# ControlPCB.net
KiCad netlist of a schematic drawn in EAGLE
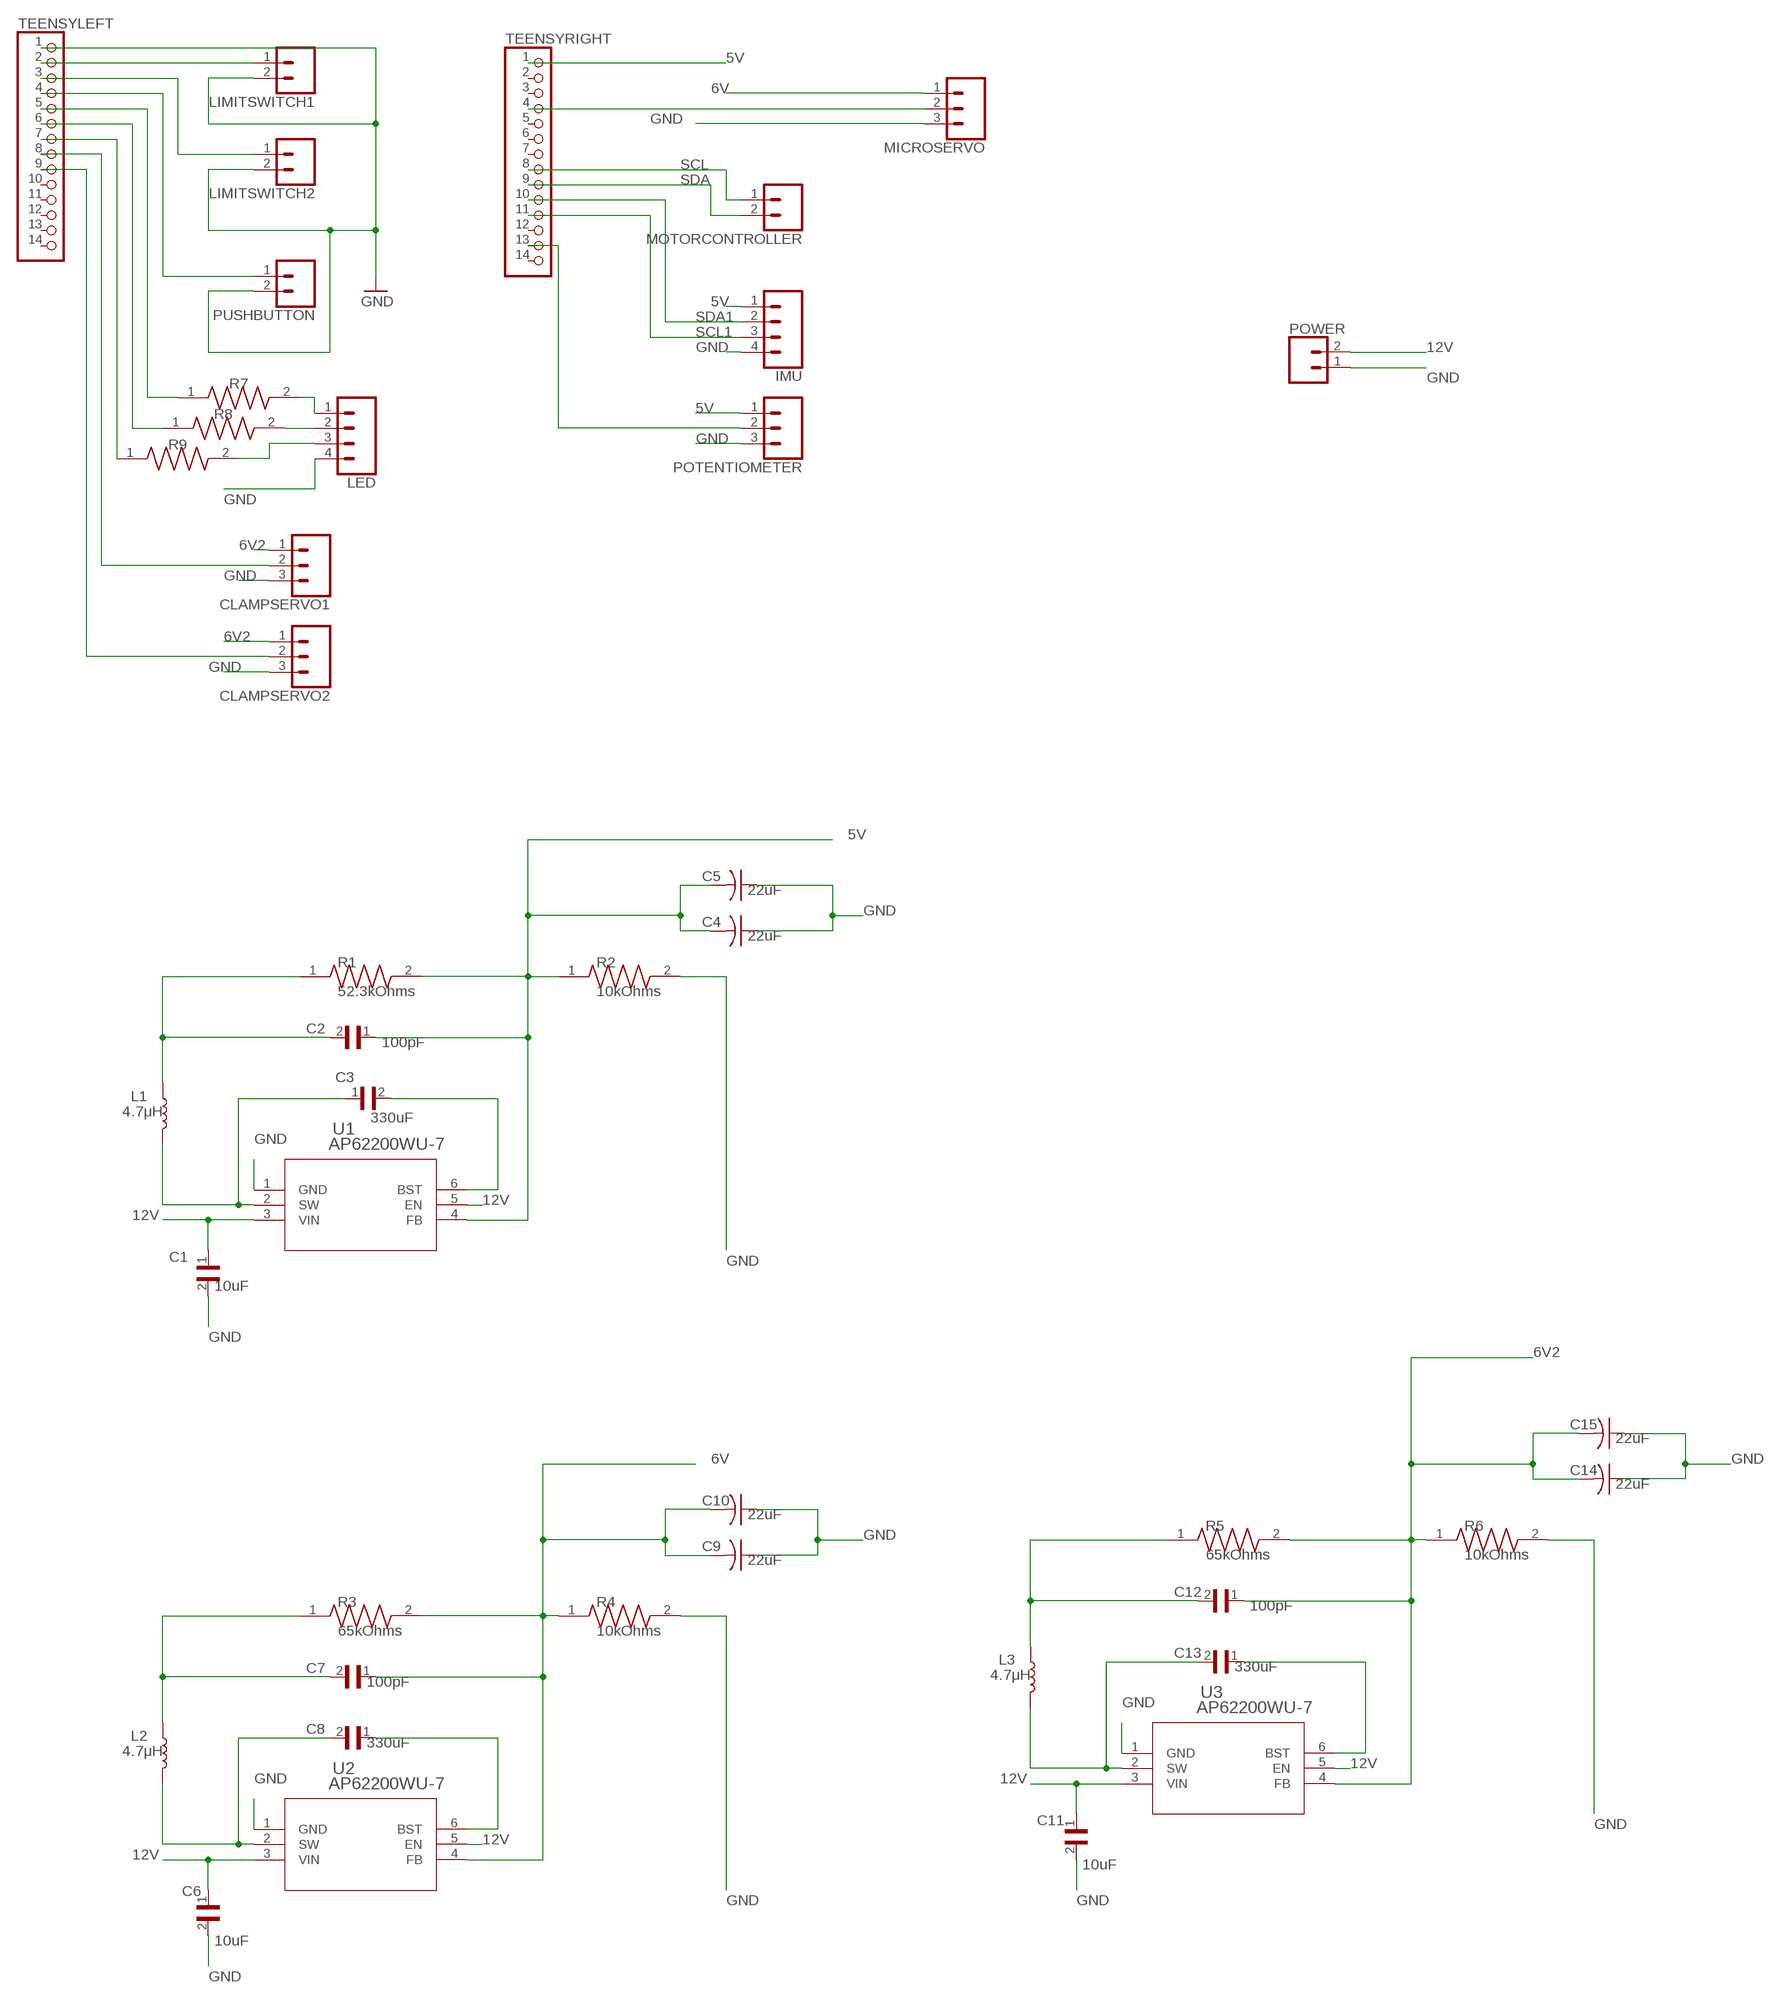
[diagram p0: schematic, sheet 1]

(export (version "E")
  (design (tool "Eeschema 10.0.6"))
  (components
    (comp (ref "C1")
      (value "10uF")
      (footprint "eagle-import:CAPC1608X90N")
      (libsource (lib "eagle-import") (part "JMK107BJ106MA-T"))
    )
    (comp (ref "C2")
      (value "100pF")
      (footprint "eagle-import:CAPC0603X33N")
      (libsource (lib "eagle-import") (part "GRM033R71E101KA01D"))
    )
    (comp (ref "C3")
      (value "330uF")
      (footprint "eagle-import:CAPC3225X280N")
      (libsource (lib "eagle-import") (part "GRM32EC80E337ME05K"))
    )
    (comp (ref "C4")
      (value "22uF")
      (footprint "eagle-import:C0402")
      (libsource (lib "eagle-import") (part "C-USC0402"))
    )
    (comp (ref "C5")
      (value "22uF")
      (footprint "eagle-import:C0402")
      (libsource (lib "eagle-import") (part "C-USC0402"))
    )
    (comp (ref "C6")
      (value "10uF")
      (footprint "eagle-import:CAPC1608X90N")
      (libsource (lib "eagle-import") (part "JMK107BJ106MA-T"))
    )
    (comp (ref "C7")
      (value "100pF")
      (footprint "eagle-import:CAPC0603X33N")
      (libsource (lib "eagle-import") (part "GRM033R71E101KA01D"))
    )
    (comp (ref "C8")
      (value "330uF")
      (footprint "eagle-import:CAPC3225X280N")
      (libsource (lib "eagle-import") (part "GRM32EC80E337ME05K"))
    )
    (comp (ref "C9")
      (value "22uF")
      (footprint "eagle-import:C0402")
      (libsource (lib "eagle-import") (part "C-USC0402"))
    )
    (comp (ref "C10")
      (value "22uF")
      (footprint "eagle-import:C0402")
      (libsource (lib "eagle-import") (part "C-USC0402"))
    )
    (comp (ref "C11")
      (value "10uF")
      (footprint "eagle-import:CAPC1608X90N")
      (libsource (lib "eagle-import") (part "JMK107BJ106MA-T"))
    )
    (comp (ref "C12")
      (value "100pF")
      (footprint "eagle-import:CAPC0603X33N")
      (libsource (lib "eagle-import") (part "GRM033R71E101KA01D"))
    )
    (comp (ref "C13")
      (value "330uF")
      (footprint "eagle-import:CAPC3225X280N")
      (libsource (lib "eagle-import") (part "GRM32EC80E337ME05K"))
    )
    (comp (ref "C14")
      (value "22uF")
      (footprint "eagle-import:C0402")
      (libsource (lib "eagle-import") (part "C-USC0402"))
    )
    (comp (ref "C15")
      (value "22uF")
      (footprint "eagle-import:C0402")
      (libsource (lib "eagle-import") (part "C-USC0402"))
    )
    (comp (ref "CLAMPSERVO1")
      (value "CONN_03SCREW")
      (footprint "eagle-import:SCREWTERMINAL-3.5MM-3")
      (libsource (lib "eagle-import") (part "CONN_03SCREW"))
    )
    (comp (ref "CLAMPSERVO2")
      (value "CONN_03SCREW")
      (footprint "eagle-import:SCREWTERMINAL-3.5MM-3")
      (libsource (lib "eagle-import") (part "CONN_03SCREW"))
    )
    (comp (ref "IMU")
      (value "CONN_04SCREW")
      (footprint "eagle-import:SCREWTERMINAL-3.5MM-4")
      (libsource (lib "eagle-import") (part "CONN_04SCREW"))
    )
    (comp (ref "L1")
      (value "4.7μH")
      (footprint "eagle-import:INDUCTOR_4X4MM")
      (libsource (lib "eagle-import") (part "4.7μH_SHIELDED_INDUCTORNPIS_LS"))
    )
    (comp (ref "L2")
      (value "4.7μH")
      (footprint "eagle-import:INDUCTOR_4X4MM")
      (libsource (lib "eagle-import") (part "4.7μH_SHIELDED_INDUCTORNPIS_LS"))
    )
    (comp (ref "L3")
      (value "4.7μH")
      (footprint "eagle-import:INDUCTOR_4X4MM")
      (libsource (lib "eagle-import") (part "4.7μH_SHIELDED_INDUCTORNPIS_LS"))
    )
    (comp (ref "LED")
      (value "CONN_04SCREW")
      (footprint "eagle-import:SCREWTERMINAL-3.5MM-4")
      (libsource (lib "eagle-import") (part "CONN_04SCREW"))
    )
    (comp (ref "LIMITSWITCH1")
      (value "CONN_023.5MM")
      (footprint "eagle-import:SCREWTERMINAL-3.5MM-2")
      (libsource (lib "eagle-import") (part "CONN_023.5MM"))
    )
    (comp (ref "LIMITSWITCH2")
      (value "CONN_023.5MM")
      (footprint "eagle-import:SCREWTERMINAL-3.5MM-2")
      (libsource (lib "eagle-import") (part "CONN_023.5MM"))
    )
    (comp (ref "MICROSERVO")
      (value "CONN_03SCREW")
      (footprint "eagle-import:SCREWTERMINAL-3.5MM-3")
      (libsource (lib "eagle-import") (part "CONN_03SCREW"))
    )
    (comp (ref "MOTORCONTROLLER")
      (value "CONN_023.5MM")
      (footprint "eagle-import:SCREWTERMINAL-3.5MM-2")
      (libsource (lib "eagle-import") (part "CONN_023.5MM"))
    )
    (comp (ref "POTENTIOMETER")
      (value "CONN_03SCREW")
      (footprint "eagle-import:SCREWTERMINAL-3.5MM-3")
      (libsource (lib "eagle-import") (part "CONN_03SCREW"))
    )
    (comp (ref "POWER")
      (value "CONN_023.5MM")
      (footprint "eagle-import:SCREWTERMINAL-3.5MM-2")
      (libsource (lib "eagle-import") (part "CONN_023.5MM"))
    )
    (comp (ref "PUSHBUTTON")
      (value "CONN_023.5MM")
      (footprint "eagle-import:SCREWTERMINAL-3.5MM-2")
      (libsource (lib "eagle-import") (part "CONN_023.5MM"))
    )
    (comp (ref "R1")
      (value "52.3kOhms")
      (footprint "eagle-import:RES_ERJ1GNF1000C")
      (fields (field (name "MANUFACTURER") "Panasonic"))
      (libsource (lib "eagle-import") (part "ERJ1GNF1000C"))
    )
    (comp (ref "R2")
      (value "10kOhms")
      (footprint "eagle-import:RES_ERJ1GNF1000C")
      (fields (field (name "MANUFACTURER") "Panasonic"))
      (libsource (lib "eagle-import") (part "ERJ1GNF1000C"))
    )
    (comp (ref "R3")
      (value "65kOhms")
      (footprint "eagle-import:RES_ERJ1GNF1000C")
      (fields (field (name "MANUFACTURER") "Panasonic"))
      (libsource (lib "eagle-import") (part "ERJ1GNF1000C"))
    )
    (comp (ref "R4")
      (value "10kOhms")
      (footprint "eagle-import:RES_ERJ1GNF1000C")
      (fields (field (name "MANUFACTURER") "Panasonic"))
      (libsource (lib "eagle-import") (part "ERJ1GNF1000C"))
    )
    (comp (ref "R5")
      (value "65kOhms")
      (footprint "eagle-import:RES_ERJ1GNF1000C")
      (fields (field (name "MANUFACTURER") "Panasonic"))
      (libsource (lib "eagle-import") (part "ERJ1GNF1000C"))
    )
    (comp (ref "R6")
      (value "10kOhms")
      (footprint "eagle-import:RES_ERJ1GNF1000C")
      (fields (field (name "MANUFACTURER") "Panasonic"))
      (libsource (lib "eagle-import") (part "ERJ1GNF1000C"))
    )
    (comp (ref "R7")
      (value "100Ohm")
      (footprint "eagle-import:RES_ERJ1GNF1000C")
      (fields (field (name "MANUFACTURER") "Panasonic"))
      (libsource (lib "eagle-import") (part "ERJ1GNF1000C"))
    )
    (comp (ref "R8")
      (value "100Ohm")
      (footprint "eagle-import:RES_ERJ1GNF1000C")
      (fields (field (name "MANUFACTURER") "Panasonic"))
      (libsource (lib "eagle-import") (part "ERJ1GNF1000C"))
    )
    (comp (ref "R9")
      (value "100Ohm")
      (footprint "eagle-import:RES_ERJ1GNF1000C")
      (fields (field (name "MANUFACTURER") "Panasonic"))
      (libsource (lib "eagle-import") (part "ERJ1GNF1000C"))
    )
    (comp (ref "TEENSYLEFT")
      (value "PINHD-1X14")
      (footprint "eagle-import:1X14")
      (libsource (lib "eagle-import") (part "PINHD-1X14"))
    )
    (comp (ref "TEENSYRIGHT")
      (value "PINHD-1X14")
      (footprint "eagle-import:1X14")
      (libsource (lib "eagle-import") (part "PINHD-1X14"))
    )
    (comp (ref "U1")
      (value "AP62200WU-7")
      (footprint "eagle-import:TSOT26-WU_DIO")
      (fields (field (name "COPYRIGHT") "Copyright (C) 2023 Ultra Librarian. All rights reserved."))
      (libsource (lib "eagle-import") (part "AP62200WU-7"))
    )
    (comp (ref "U2")
      (value "AP62200WU-7")
      (footprint "eagle-import:TSOT26-WU_DIO")
      (fields (field (name "COPYRIGHT") "Copyright (C) 2023 Ultra Librarian. All rights reserved."))
      (libsource (lib "eagle-import") (part "AP62200WU-7"))
    )
    (comp (ref "U3")
      (value "AP62200WU-7")
      (footprint "eagle-import:TSOT26-WU_DIO")
      (fields (field (name "COPYRIGHT") "Copyright (C) 2023 Ultra Librarian. All rights reserved."))
      (libsource (lib "eagle-import") (part "AP62200WU-7"))
    )
  )
  (nets
    (net (code "1") (name "/5V") (class "Default")
      (node (ref "C2") (pin "1") (pinfunction "1_1") (pintype "passive"))
      (node (ref "C4") (pin "2") (pinfunction "2_2") (pintype "passive"))
      (node (ref "C5") (pin "2") (pinfunction "2_2") (pintype "passive"))
      (node (ref "IMU") (pin "1") (pinfunction "1_1") (pintype "passive"))
      (node (ref "POTENTIOMETER") (pin "1") (pinfunction "1_1") (pintype "passive"))
      (node (ref "R1") (pin "2") (pinfunction "2_2") (pintype "passive"))
      (node (ref "R2") (pin "1") (pinfunction "1_1") (pintype "passive"))
      (node (ref "TEENSYRIGHT") (pin "1") (pinfunction "1_1") (pintype "passive"))
      (node (ref "U1") (pin "4") (pinfunction "FB_4") (pintype "passive"))
    )
    (net (code "2") (name "/6V") (class "Default")
      (node (ref "C10") (pin "2") (pinfunction "2_2") (pintype "passive"))
      (node (ref "C7") (pin "1") (pinfunction "1_1") (pintype "passive"))
      (node (ref "C9") (pin "2") (pinfunction "2_2") (pintype "passive"))
      (node (ref "MICROSERVO") (pin "1") (pinfunction "1_1") (pintype "passive"))
      (node (ref "R3") (pin "2") (pinfunction "2_2") (pintype "passive"))
      (node (ref "R4") (pin "1") (pinfunction "1_1") (pintype "passive"))
      (node (ref "U2") (pin "4") (pinfunction "FB_4") (pintype "passive"))
    )
    (net (code "3") (name "/6V2") (class "Default")
      (node (ref "C12") (pin "1") (pinfunction "1_1") (pintype "passive"))
      (node (ref "C14") (pin "2") (pinfunction "2_2") (pintype "passive"))
      (node (ref "C15") (pin "2") (pinfunction "2_2") (pintype "passive"))
      (node (ref "CLAMPSERVO1") (pin "1") (pinfunction "1_1") (pintype "passive"))
      (node (ref "CLAMPSERVO2") (pin "1") (pinfunction "1_1") (pintype "passive"))
      (node (ref "R5") (pin "2") (pinfunction "2_2") (pintype "passive"))
      (node (ref "R6") (pin "1") (pinfunction "1_1") (pintype "passive"))
      (node (ref "U3") (pin "4") (pinfunction "FB_4") (pintype "passive"))
    )
    (net (code "4") (name "/12V") (class "Default")
      (node (ref "C1") (pin "1") (pinfunction "1_1") (pintype "passive"))
      (node (ref "C11") (pin "1") (pinfunction "1_1") (pintype "passive"))
      (node (ref "C6") (pin "1") (pinfunction "1_1") (pintype "passive"))
      (node (ref "POWER") (pin "2") (pinfunction "2_2") (pintype "passive"))
      (node (ref "U1") (pin "3") (pinfunction "VIN_3") (pintype "power_in"))
      (node (ref "U1") (pin "5") (pinfunction "EN_5") (pintype "input"))
      (node (ref "U2") (pin "3") (pinfunction "VIN_3") (pintype "power_in"))
      (node (ref "U2") (pin "5") (pinfunction "EN_5") (pintype "input"))
      (node (ref "U3") (pin "3") (pinfunction "VIN_3") (pintype "power_in"))
      (node (ref "U3") (pin "5") (pinfunction "EN_5") (pintype "input"))
    )
    (net (code "5") (name "/SCL") (class "Default")
      (node (ref "MOTORCONTROLLER") (pin "1") (pinfunction "1_1") (pintype "passive"))
      (node (ref "TEENSYRIGHT") (pin "8") (pinfunction "8_8") (pintype "passive"))
    )
    (net (code "6") (name "/SCL1") (class "Default")
      (node (ref "IMU") (pin "3") (pinfunction "3_3") (pintype "passive"))
      (node (ref "TEENSYRIGHT") (pin "11") (pinfunction "11_11") (pintype "passive"))
    )
    (net (code "7") (name "/SDA") (class "Default")
      (node (ref "MOTORCONTROLLER") (pin "2") (pinfunction "2_2") (pintype "passive"))
      (node (ref "TEENSYRIGHT") (pin "9") (pinfunction "9_9") (pintype "passive"))
    )
    (net (code "8") (name "/SDA1") (class "Default")
      (node (ref "IMU") (pin "2") (pinfunction "2_2") (pintype "passive"))
      (node (ref "TEENSYRIGHT") (pin "10") (pinfunction "10_10") (pintype "passive"))
    )
    (net (code "9") (name "GND") (class "Default")
      (node (ref "C1") (pin "2") (pinfunction "2_2") (pintype "passive"))
      (node (ref "C10") (pin "1") (pinfunction "1_1") (pintype "passive"))
      (node (ref "C11") (pin "2") (pinfunction "2_2") (pintype "passive"))
      (node (ref "C14") (pin "1") (pinfunction "1_1") (pintype "passive"))
      (node (ref "C15") (pin "1") (pinfunction "1_1") (pintype "passive"))
      (node (ref "C4") (pin "1") (pinfunction "1_1") (pintype "passive"))
      (node (ref "C5") (pin "1") (pinfunction "1_1") (pintype "passive"))
      (node (ref "C6") (pin "2") (pinfunction "2_2") (pintype "passive"))
      (node (ref "C9") (pin "1") (pinfunction "1_1") (pintype "passive"))
      (node (ref "CLAMPSERVO1") (pin "3") (pinfunction "3_3") (pintype "passive"))
      (node (ref "CLAMPSERVO2") (pin "3") (pinfunction "3_3") (pintype "passive"))
      (node (ref "IMU") (pin "4") (pinfunction "4_4") (pintype "passive"))
      (node (ref "LED") (pin "4") (pinfunction "4_4") (pintype "passive"))
      (node (ref "LIMITSWITCH1") (pin "2") (pinfunction "2_2") (pintype "passive"))
      (node (ref "LIMITSWITCH2") (pin "2") (pinfunction "2_2") (pintype "passive"))
      (node (ref "MICROSERVO") (pin "3") (pinfunction "3_3") (pintype "passive"))
      (node (ref "POTENTIOMETER") (pin "3") (pinfunction "3_3") (pintype "passive"))
      (node (ref "POWER") (pin "1") (pinfunction "1_1") (pintype "passive"))
      (node (ref "PUSHBUTTON") (pin "2") (pinfunction "2_2") (pintype "passive"))
      (node (ref "R2") (pin "2") (pinfunction "2_2") (pintype "passive"))
      (node (ref "R4") (pin "2") (pinfunction "2_2") (pintype "passive"))
      (node (ref "R6") (pin "2") (pinfunction "2_2") (pintype "passive"))
      (node (ref "TEENSYLEFT") (pin "1") (pinfunction "1_1") (pintype "passive"))
      (node (ref "U1") (pin "1") (pinfunction "GND_1") (pintype "passive"))
      (node (ref "U2") (pin "1") (pinfunction "GND_1") (pintype "passive"))
      (node (ref "U3") (pin "1") (pinfunction "GND_1") (pintype "passive"))
    )
    (net (code "10") (name "Net-(CLAMPSERVO1-Pad2)") (class "Default")
      (node (ref "CLAMPSERVO1") (pin "2") (pinfunction "2_2") (pintype "passive"))
      (node (ref "TEENSYLEFT") (pin "8") (pinfunction "8_8") (pintype "passive"))
    )
    (net (code "11") (name "Net-(CLAMPSERVO2-Pad2)") (class "Default")
      (node (ref "CLAMPSERVO2") (pin "2") (pinfunction "2_2") (pintype "passive"))
      (node (ref "TEENSYLEFT") (pin "9") (pinfunction "9_9") (pintype "passive"))
    )
    (net (code "12") (name "Net-(L1-1)") (class "Default")
      (node (ref "C2") (pin "2") (pinfunction "2_2") (pintype "passive"))
      (node (ref "L1") (pin "P$1") (pinfunction "1_P$1") (pintype "passive"))
      (node (ref "R1") (pin "1") (pinfunction "1_1") (pintype "passive"))
    )
    (net (code "13") (name "Net-(L1-2)") (class "Default")
      (node (ref "C3") (pin "1") (pinfunction "1_1") (pintype "passive"))
      (node (ref "L1") (pin "P$2") (pinfunction "2_P$2") (pintype "passive"))
      (node (ref "U1") (pin "2") (pinfunction "SW_2") (pintype "passive"))
    )
    (net (code "14") (name "Net-(L2-1)") (class "Default")
      (node (ref "C7") (pin "2") (pinfunction "2_2") (pintype "passive"))
      (node (ref "L2") (pin "P$1") (pinfunction "1_P$1") (pintype "passive"))
      (node (ref "R3") (pin "1") (pinfunction "1_1") (pintype "passive"))
    )
    (net (code "15") (name "Net-(L2-2)") (class "Default")
      (node (ref "C8") (pin "2") (pinfunction "2_2") (pintype "passive"))
      (node (ref "L2") (pin "P$2") (pinfunction "2_P$2") (pintype "passive"))
      (node (ref "U2") (pin "2") (pinfunction "SW_2") (pintype "passive"))
    )
    (net (code "16") (name "Net-(L3-1)") (class "Default")
      (node (ref "C12") (pin "2") (pinfunction "2_2") (pintype "passive"))
      (node (ref "L3") (pin "P$1") (pinfunction "1_P$1") (pintype "passive"))
      (node (ref "R5") (pin "1") (pinfunction "1_1") (pintype "passive"))
    )
    (net (code "17") (name "Net-(L3-2)") (class "Default")
      (node (ref "C13") (pin "2") (pinfunction "2_2") (pintype "passive"))
      (node (ref "L3") (pin "P$2") (pinfunction "2_P$2") (pintype "passive"))
      (node (ref "U3") (pin "2") (pinfunction "SW_2") (pintype "passive"))
    )
    (net (code "18") (name "Net-(LED-Pad1)") (class "Default")
      (node (ref "LED") (pin "1") (pinfunction "1_1") (pintype "passive"))
      (node (ref "R7") (pin "2") (pinfunction "2_2") (pintype "passive"))
    )
    (net (code "19") (name "Net-(LED-Pad2)") (class "Default")
      (node (ref "LED") (pin "2") (pinfunction "2_2") (pintype "passive"))
      (node (ref "R8") (pin "2") (pinfunction "2_2") (pintype "passive"))
    )
    (net (code "20") (name "Net-(LED-Pad3)") (class "Default")
      (node (ref "LED") (pin "3") (pinfunction "3_3") (pintype "passive"))
      (node (ref "R9") (pin "2") (pinfunction "2_2") (pintype "passive"))
    )
    (net (code "21") (name "Net-(LIMITSWITCH1-Pad1)") (class "Default")
      (node (ref "LIMITSWITCH1") (pin "1") (pinfunction "1_1") (pintype "passive"))
      (node (ref "TEENSYLEFT") (pin "2") (pinfunction "2_2") (pintype "passive"))
    )
    (net (code "22") (name "Net-(LIMITSWITCH2-Pad1)") (class "Default")
      (node (ref "LIMITSWITCH2") (pin "1") (pinfunction "1_1") (pintype "passive"))
      (node (ref "TEENSYLEFT") (pin "3") (pinfunction "3_3") (pintype "passive"))
    )
    (net (code "23") (name "Net-(MICROSERVO-Pad2)") (class "Default")
      (node (ref "MICROSERVO") (pin "2") (pinfunction "2_2") (pintype "passive"))
      (node (ref "TEENSYRIGHT") (pin "4") (pinfunction "4_4") (pintype "passive"))
    )
    (net (code "24") (name "Net-(POTENTIOMETER-Pad2)") (class "Default")
      (node (ref "POTENTIOMETER") (pin "2") (pinfunction "2_2") (pintype "passive"))
      (node (ref "TEENSYRIGHT") (pin "13") (pinfunction "13_13") (pintype "passive"))
    )
    (net (code "25") (name "Net-(PUSHBUTTON-Pad1)") (class "Default")
      (node (ref "PUSHBUTTON") (pin "1") (pinfunction "1_1") (pintype "passive"))
      (node (ref "TEENSYLEFT") (pin "4") (pinfunction "4_4") (pintype "passive"))
    )
    (net (code "26") (name "Net-(R7-Pad1)") (class "Default")
      (node (ref "R7") (pin "1") (pinfunction "1_1") (pintype "passive"))
      (node (ref "TEENSYLEFT") (pin "5") (pinfunction "5_5") (pintype "passive"))
    )
    (net (code "27") (name "Net-(R8-Pad1)") (class "Default")
      (node (ref "R8") (pin "1") (pinfunction "1_1") (pintype "passive"))
      (node (ref "TEENSYLEFT") (pin "6") (pinfunction "6_6") (pintype "passive"))
    )
    (net (code "28") (name "Net-(R9-Pad1)") (class "Default")
      (node (ref "R9") (pin "1") (pinfunction "1_1") (pintype "passive"))
      (node (ref "TEENSYLEFT") (pin "7") (pinfunction "7_7") (pintype "passive"))
    )
    (net (code "29") (name "Net-(U1-BST)") (class "Default")
      (node (ref "C3") (pin "2") (pinfunction "2_2") (pintype "passive"))
      (node (ref "U1") (pin "6") (pinfunction "BST_6") (pintype "input"))
    )
    (net (code "30") (name "Net-(U2-BST)") (class "Default")
      (node (ref "C8") (pin "1") (pinfunction "1_1") (pintype "passive"))
      (node (ref "U2") (pin "6") (pinfunction "BST_6") (pintype "input"))
    )
    (net (code "31") (name "Net-(U3-BST)") (class "Default")
      (node (ref "C13") (pin "1") (pinfunction "1_1") (pintype "passive"))
      (node (ref "U3") (pin "6") (pinfunction "BST_6") (pintype "input"))
    )
    (net (code "32") (name "unconnected-(TEENSYLEFT-Pad10)") (class "Default")
      (node (ref "TEENSYLEFT") (pin "10") (pinfunction "10_10") (pintype "passive"))
    )
    (net (code "33") (name "unconnected-(TEENSYLEFT-Pad11)") (class "Default")
      (node (ref "TEENSYLEFT") (pin "11") (pinfunction "11_11") (pintype "passive"))
    )
    (net (code "34") (name "unconnected-(TEENSYLEFT-Pad12)") (class "Default")
      (node (ref "TEENSYLEFT") (pin "12") (pinfunction "12_12") (pintype "passive"))
    )
    (net (code "35") (name "unconnected-(TEENSYLEFT-Pad13)") (class "Default")
      (node (ref "TEENSYLEFT") (pin "13") (pinfunction "13_13") (pintype "passive"))
    )
    (net (code "36") (name "unconnected-(TEENSYLEFT-Pad14)") (class "Default")
      (node (ref "TEENSYLEFT") (pin "14") (pinfunction "14_14") (pintype "passive"))
    )
    (net (code "37") (name "unconnected-(TEENSYRIGHT-Pad2)") (class "Default")
      (node (ref "TEENSYRIGHT") (pin "2") (pinfunction "2_2") (pintype "passive"))
    )
    (net (code "38") (name "unconnected-(TEENSYRIGHT-Pad3)") (class "Default")
      (node (ref "TEENSYRIGHT") (pin "3") (pinfunction "3_3") (pintype "passive"))
    )
    (net (code "39") (name "unconnected-(TEENSYRIGHT-Pad5)") (class "Default")
      (node (ref "TEENSYRIGHT") (pin "5") (pinfunction "5_5") (pintype "passive"))
    )
    (net (code "40") (name "unconnected-(TEENSYRIGHT-Pad6)") (class "Default")
      (node (ref "TEENSYRIGHT") (pin "6") (pinfunction "6_6") (pintype "passive"))
    )
    (net (code "41") (name "unconnected-(TEENSYRIGHT-Pad7)") (class "Default")
      (node (ref "TEENSYRIGHT") (pin "7") (pinfunction "7_7") (pintype "passive"))
    )
    (net (code "42") (name "unconnected-(TEENSYRIGHT-Pad12)") (class "Default")
      (node (ref "TEENSYRIGHT") (pin "12") (pinfunction "12_12") (pintype "passive"))
    )
    (net (code "43") (name "unconnected-(TEENSYRIGHT-Pad14)") (class "Default")
      (node (ref "TEENSYRIGHT") (pin "14") (pinfunction "14_14") (pintype "passive"))
    )
  )
)
